# MODUL_TEMPERATURE_V100.net
KiCad netlist of a schematic drawn in EAGLE
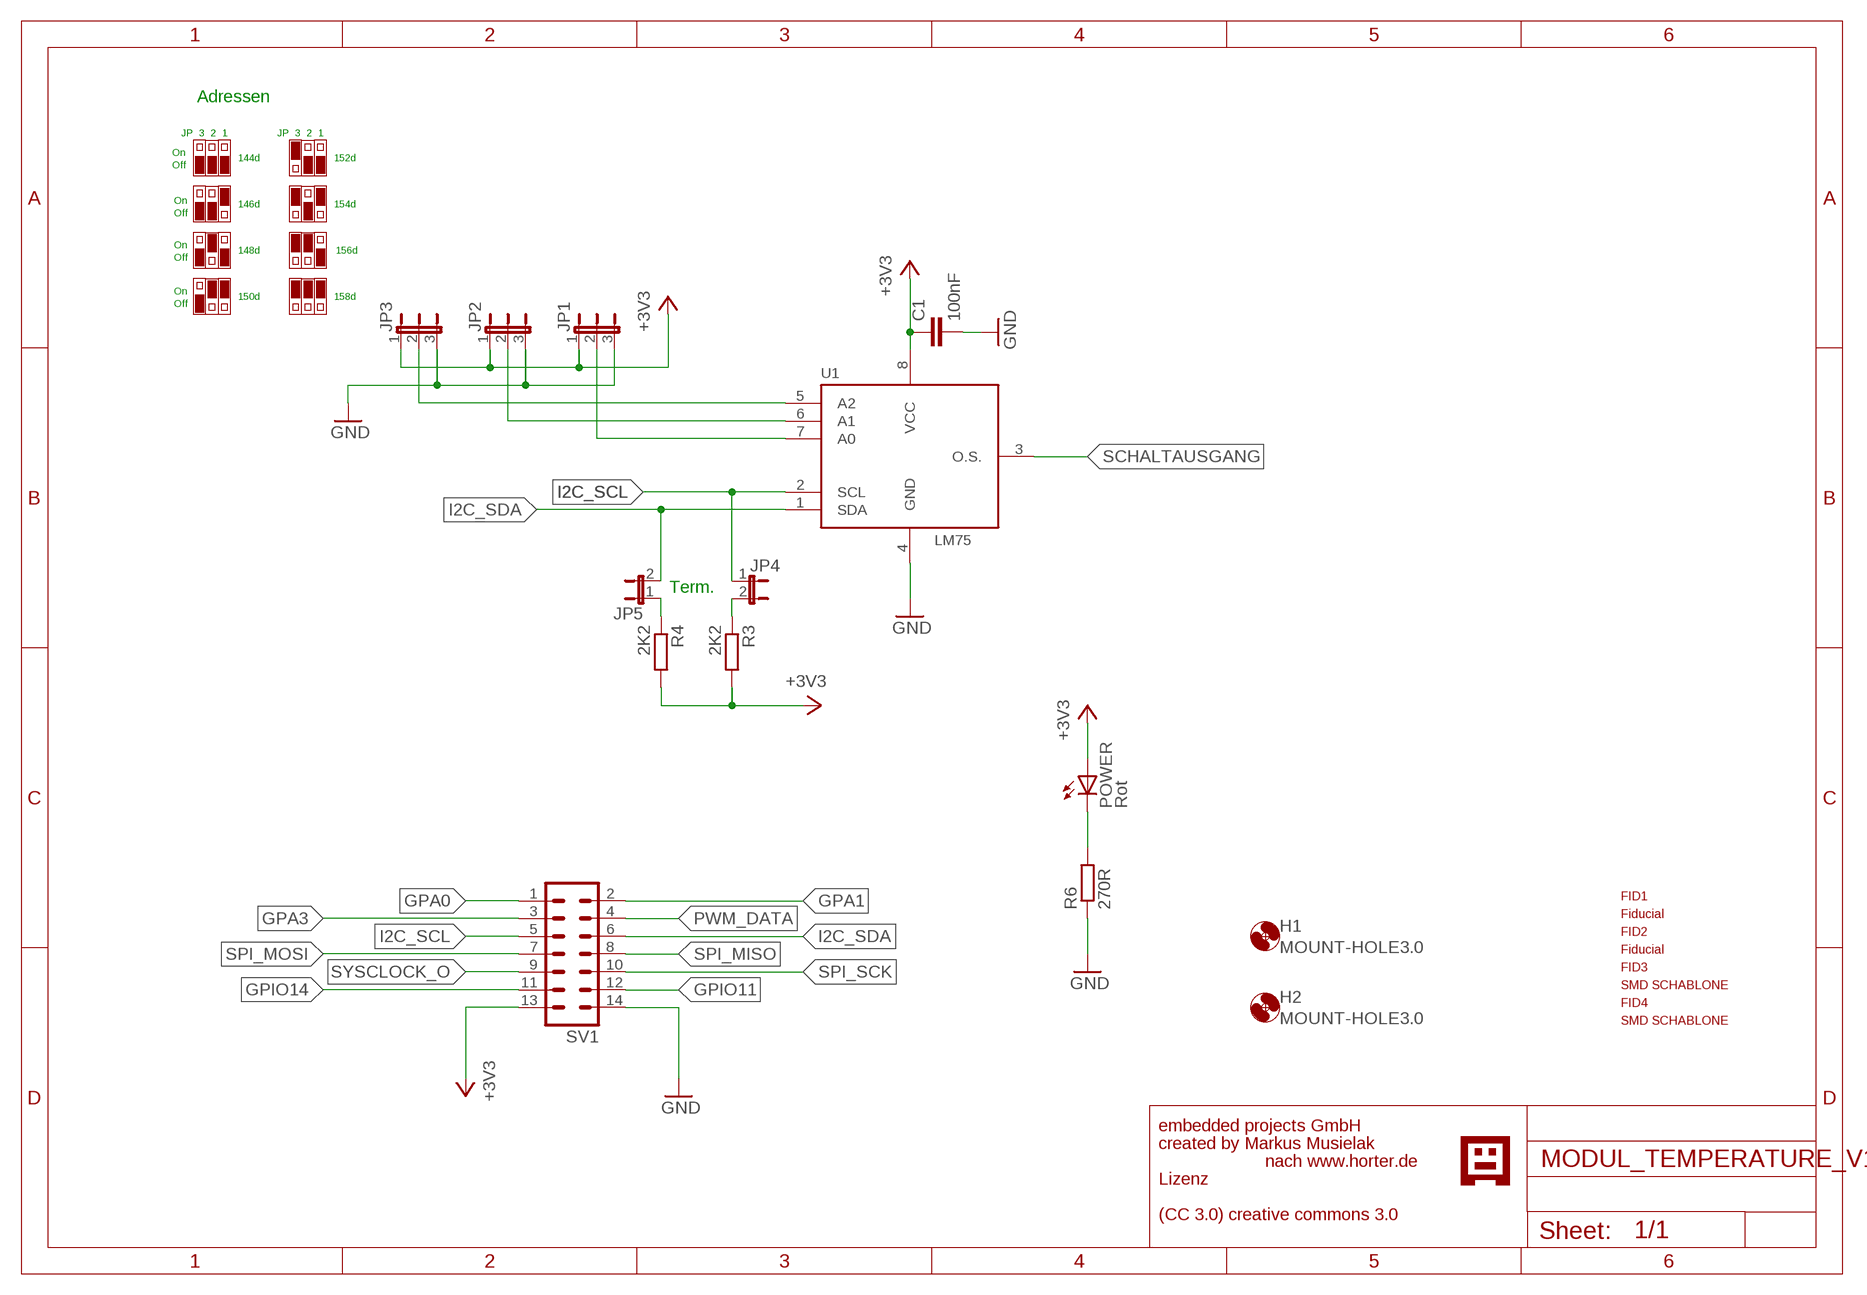
[diagram p0: schematic, sheet 1]

(export (version "E")
  (design (tool "Eeschema 10.0.6"))
  (components
    (comp (ref "C1")
      (value "100nF")
      (footprint "eagle-import:C0805")
      (libsource (lib "eagle-import") (part "C-EUC0805"))
    )
    (comp (ref "FID1")
      (value "PASSERMARKEN_FIDUCIAL")
      (footprint "eagle-import:PASSERMARKEN_FIDUCIAL")
      (libsource (lib "eagle-import") (part "PASSERMARKEN_FIDUCIAL"))
    )
    (comp (ref "FID2")
      (value "PASSERMARKEN_FIDUCIAL")
      (footprint "eagle-import:PASSERMARKEN_FIDUCIAL")
      (libsource (lib "eagle-import") (part "PASSERMARKEN_FIDUCIAL"))
    )
    (comp (ref "FID3")
      (value "PASSERMARKEN_FIDUCIAL")
      (footprint "eagle-import:PASSERMARKEN_FIDUCIAL")
      (libsource (lib "eagle-import") (part "SMDSCHABLONE_PASSERMARKEN_FIDUCIAL"))
    )
    (comp (ref "FID4")
      (value "PASSERMARKEN_FIDUCIAL")
      (footprint "eagle-import:PASSERMARKEN_FIDUCIAL")
      (libsource (lib "eagle-import") (part "SMDSCHABLONE_PASSERMARKEN_FIDUCIAL"))
    )
    (comp (ref "H1")
      (value "MOUNT-HOLE3.0")
      (footprint "eagle-import:3,0")
      (libsource (lib "eagle-import") (part "MOUNT-HOLE3.0"))
    )
    (comp (ref "H2")
      (value "MOUNT-HOLE3.0")
      (footprint "eagle-import:3,0")
      (libsource (lib "eagle-import") (part "MOUNT-HOLE3.0"))
    )
    (comp (ref "JP1")
      (value "JP2E")
      (footprint "eagle-import:JP2")
      (libsource (lib "eagle-import") (part "JP2E"))
    )
    (comp (ref "JP2")
      (value "JP2E")
      (footprint "eagle-import:JP2")
      (libsource (lib "eagle-import") (part "JP2E"))
    )
    (comp (ref "JP3")
      (value "JP2E")
      (footprint "eagle-import:JP2")
      (libsource (lib "eagle-import") (part "JP2E"))
    )
    (comp (ref "JP4")
      (value "JP1E")
      (footprint "eagle-import:JP1")
      (libsource (lib "eagle-import") (part "JP1E"))
    )
    (comp (ref "JP5")
      (value "JP1E")
      (footprint "eagle-import:JP1")
      (libsource (lib "eagle-import") (part "JP1E"))
    )
    (comp (ref "POWER")
      (value "Rot")
      (footprint "eagle-import:CHIP-LED0805")
      (libsource (lib "eagle-import") (part "LEDCHIP-LED0805"))
    )
    (comp (ref "R3")
      (value "2K2")
      (footprint "eagle-import:R0805")
      (libsource (lib "eagle-import") (part "R-EU_R0805"))
    )
    (comp (ref "R4")
      (value "2K2")
      (footprint "eagle-import:R0805")
      (libsource (lib "eagle-import") (part "R-EU_R0805"))
    )
    (comp (ref "R6")
      (value "270R")
      (footprint "eagle-import:R0805")
      (libsource (lib "eagle-import") (part "R-EU_R0805"))
    )
    (comp (ref "SV1")
      (value "ML14")
      (footprint "eagle-import:ML14")
      (libsource (lib "eagle-import") (part "ML14"))
    )
    (comp (ref "U$1")
      (value "GNUBLINLOGOSIEB")
      (footprint "eagle-import:GNUSIEBDRUCK")
      (libsource (lib "eagle-import") (part "GNUBLINLOGOSIEB"))
    )
    (comp (ref "U1")
      (value "LM75")
      (footprint "eagle-import:SO-8")
      (libsource (lib "eagle-import") (part "LM75"))
    )
  )
  (nets
    (net (code "1") (name "+3V3") (class "Default")
      (node (ref "C1") (pin "1") (pinfunction "1_1") (pintype "passive"))
      (node (ref "JP1") (pin "1") (pinfunction "1_1") (pintype "passive"))
      (node (ref "JP2") (pin "1") (pinfunction "1_1") (pintype "passive"))
      (node (ref "JP3") (pin "1") (pinfunction "1_1") (pintype "passive"))
      (node (ref "POWER") (pin "A") (pinfunction "A_A") (pintype "passive"))
      (node (ref "R3") (pin "2") (pinfunction "2_2") (pintype "passive"))
      (node (ref "R4") (pin "2") (pinfunction "2_2") (pintype "passive"))
      (node (ref "SV1") (pin "13") (pinfunction "13_13") (pintype "passive"))
      (node (ref "U1") (pin "8") (pinfunction "VCC_8") (pintype "power_in"))
    )
    (net (code "2") (name "GND") (class "Default")
      (node (ref "C1") (pin "2") (pinfunction "2_2") (pintype "passive"))
      (node (ref "JP1") (pin "3") (pinfunction "3_3") (pintype "passive"))
      (node (ref "JP2") (pin "3") (pinfunction "3_3") (pintype "passive"))
      (node (ref "JP3") (pin "3") (pinfunction "3_3") (pintype "passive"))
      (node (ref "R6") (pin "1") (pinfunction "1_1") (pintype "passive"))
      (node (ref "SV1") (pin "14") (pinfunction "14_14") (pintype "passive"))
      (node (ref "U1") (pin "4") (pinfunction "GND_4") (pintype "power_in"))
    )
    (net (code "3") (name "GPA0") (class "Default")
      (node (ref "SV1") (pin "1") (pinfunction "1_1") (pintype "passive"))
    )
    (net (code "4") (name "GPA1") (class "Default")
      (node (ref "SV1") (pin "2") (pinfunction "2_2") (pintype "passive"))
    )
    (net (code "5") (name "GPA3") (class "Default")
      (node (ref "SV1") (pin "3") (pinfunction "3_3") (pintype "passive"))
    )
    (net (code "6") (name "GPIO11") (class "Default")
      (node (ref "SV1") (pin "12") (pinfunction "12_12") (pintype "passive"))
    )
    (net (code "7") (name "GPIO14") (class "Default")
      (node (ref "SV1") (pin "11") (pinfunction "11_11") (pintype "passive"))
    )
    (net (code "8") (name "I2C_SCL") (class "Default")
      (node (ref "JP4") (pin "1") (pinfunction "1_1") (pintype "passive"))
      (node (ref "SV1") (pin "5") (pinfunction "5_5") (pintype "passive"))
      (node (ref "U1") (pin "2") (pinfunction "SCL_2") (pintype "input"))
    )
    (net (code "9") (name "I2C_SDA") (class "Default")
      (node (ref "JP5") (pin "2") (pinfunction "2_2") (pintype "passive"))
      (node (ref "SV1") (pin "6") (pinfunction "6_6") (pintype "passive"))
      (node (ref "U1") (pin "1") (pinfunction "SDA_1") (pintype "bidirectional"))
    )
    (net (code "10") (name "Net-(JP4-Pad2)") (class "Default")
      (node (ref "JP4") (pin "2") (pinfunction "2_2") (pintype "passive"))
      (node (ref "R3") (pin "1") (pinfunction "1_1") (pintype "passive"))
    )
    (net (code "11") (name "Net-(JP5-Pad1)") (class "Default")
      (node (ref "JP5") (pin "1") (pinfunction "1_1") (pintype "passive"))
      (node (ref "R4") (pin "1") (pinfunction "1_1") (pintype "passive"))
    )
    (net (code "12") (name "Net-(POWER-PadC)") (class "Default")
      (node (ref "POWER") (pin "C") (pinfunction "C_C") (pintype "passive"))
      (node (ref "R6") (pin "2") (pinfunction "2_2") (pintype "passive"))
    )
    (net (code "13") (name "Net-(U1-A0)") (class "Default")
      (node (ref "JP1") (pin "2") (pinfunction "2_2") (pintype "passive"))
      (node (ref "U1") (pin "7") (pinfunction "A0_7") (pintype "input"))
    )
    (net (code "14") (name "Net-(U1-A1)") (class "Default")
      (node (ref "JP2") (pin "2") (pinfunction "2_2") (pintype "passive"))
      (node (ref "U1") (pin "6") (pinfunction "A1_6") (pintype "input"))
    )
    (net (code "15") (name "Net-(U1-A2)") (class "Default")
      (node (ref "JP3") (pin "2") (pinfunction "2_2") (pintype "passive"))
      (node (ref "U1") (pin "5") (pinfunction "A2_5") (pintype "input"))
    )
    (net (code "16") (name "PWM_DATA") (class "Default")
      (node (ref "SV1") (pin "4") (pinfunction "4_4") (pintype "passive"))
    )
    (net (code "17") (name "SCHALTAUSGANG") (class "Default")
      (node (ref "U1") (pin "3") (pinfunction "O.S._3") (pintype "output"))
    )
    (net (code "18") (name "SPI_MISO") (class "Default")
      (node (ref "SV1") (pin "8") (pinfunction "8_8") (pintype "passive"))
    )
    (net (code "19") (name "SPI_MOSI") (class "Default")
      (node (ref "SV1") (pin "7") (pinfunction "7_7") (pintype "passive"))
    )
    (net (code "20") (name "SPI_SCK") (class "Default")
      (node (ref "SV1") (pin "10") (pinfunction "10_10") (pintype "passive"))
    )
    (net (code "21") (name "SYSCLOCK_O") (class "Default")
      (node (ref "SV1") (pin "9") (pinfunction "9_9") (pintype "passive"))
    )
  )
)
